# BlueFly-Shield_v10.net
KiCad netlist of a schematic drawn in EAGLE
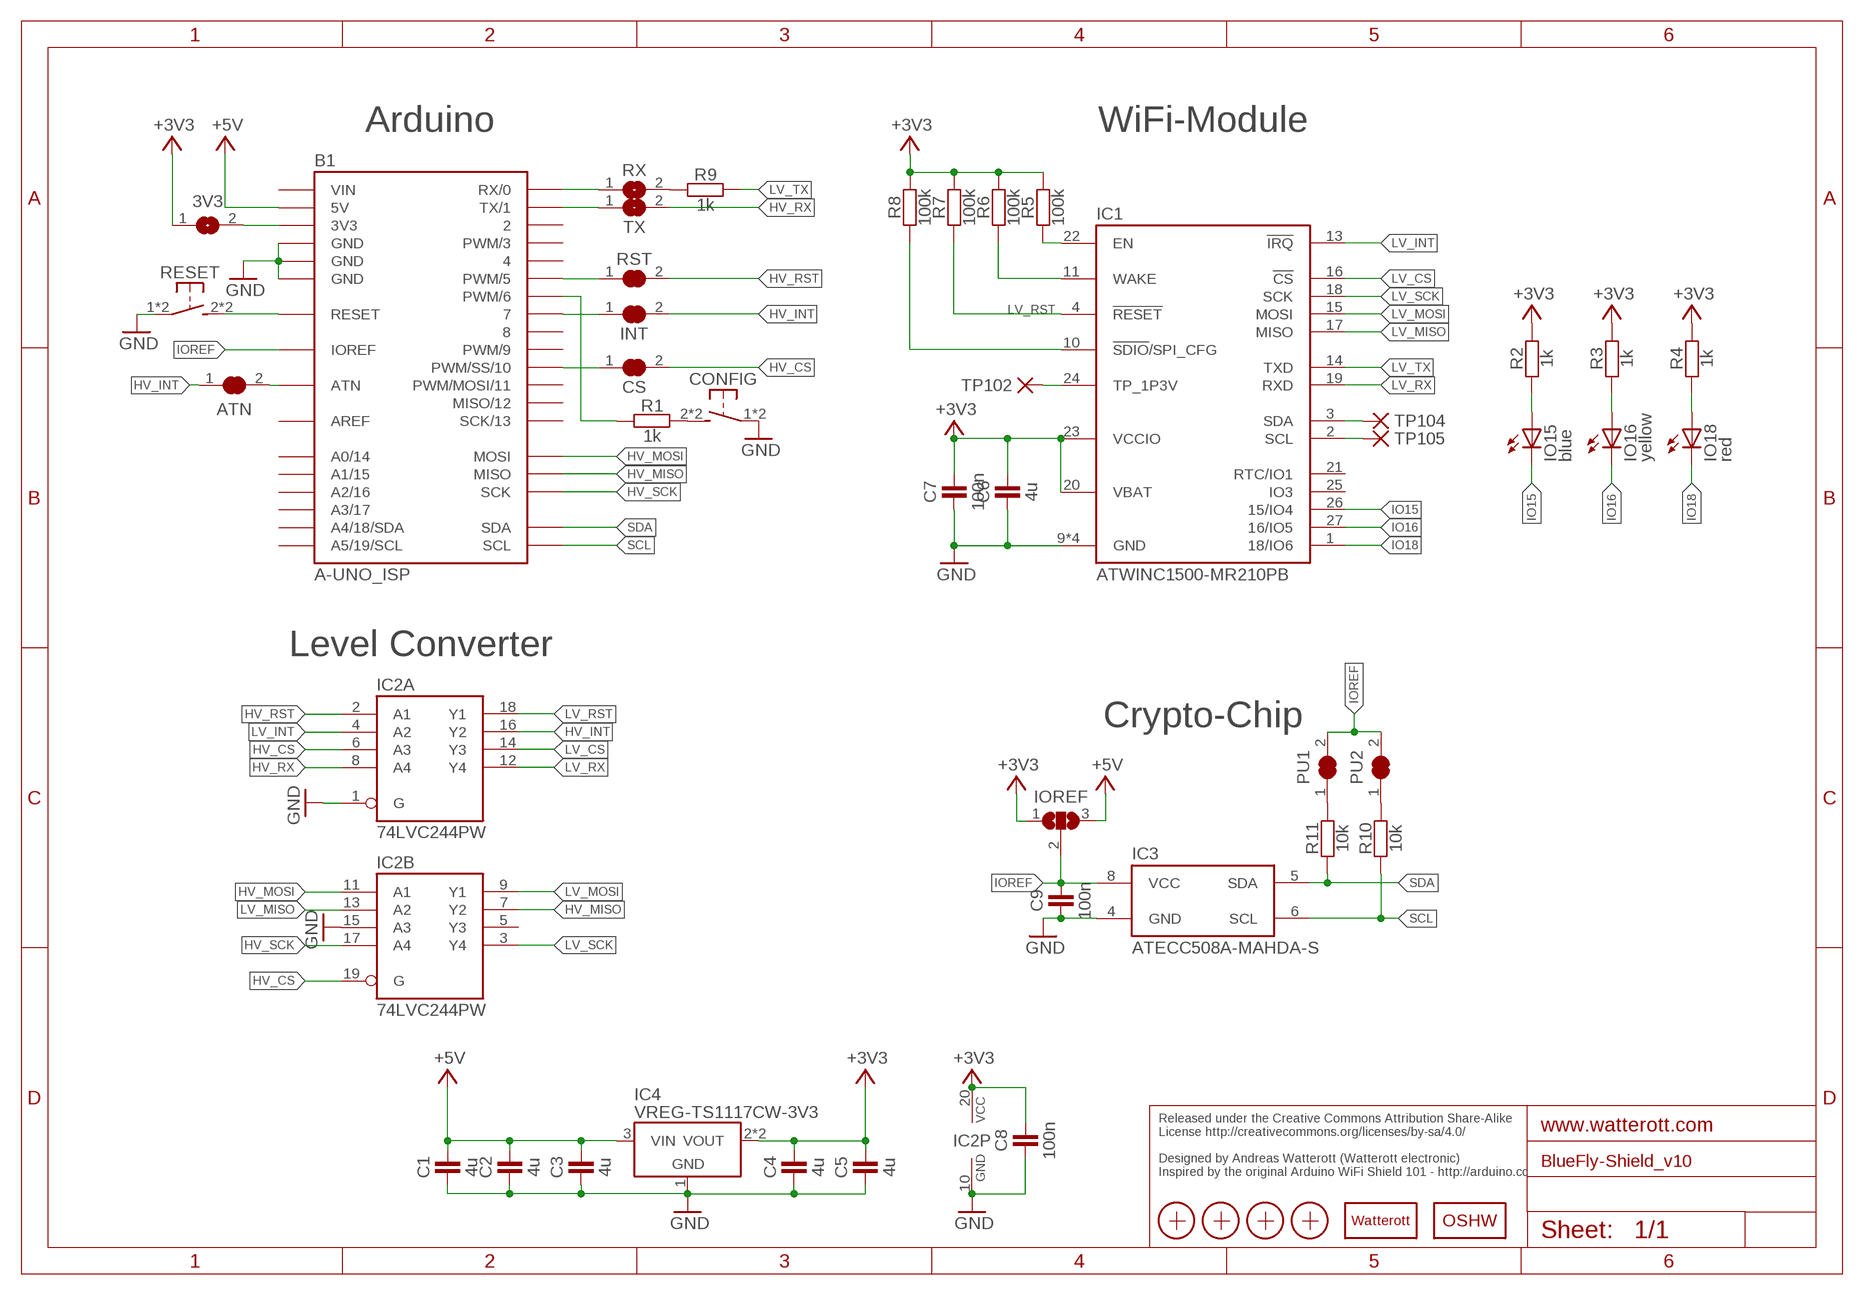
[diagram p0: schematic, sheet 1]

(export (version "E")
  (design (tool "Eeschema 10.0.6"))
  (components
    (comp (ref "3V3")
      (value "JUMPER2-0603-NC")
      (footprint "eagle-import:JUMPER2-0603_NC")
      (libsource (lib "eagle-import") (part "JUMPER2-0603-NC"))
    )
    (comp (ref "ATN")
      (value "JUMPER2-0603-NC")
      (footprint "eagle-import:JUMPER2-0603_NC")
      (libsource (lib "eagle-import") (part "JUMPER2-0603-NC"))
    )
    (comp (ref "B1")
      (value "A-UNO_ISP")
      (footprint "eagle-import:A-UNO-ISP")
      (libsource (lib "eagle-import") (part "A-UNO_ISP"))
    )
    (comp (ref "C1")
      (value "4u")
      (footprint "eagle-import:C0603")
      (libsource (lib "eagle-import") (part "CAPACITOR-0603"))
    )
    (comp (ref "C2")
      (value "4u")
      (footprint "eagle-import:C0603")
      (libsource (lib "eagle-import") (part "CAPACITOR-0603"))
    )
    (comp (ref "C3")
      (value "4u")
      (footprint "eagle-import:C0603")
      (libsource (lib "eagle-import") (part "CAPACITOR-0603"))
    )
    (comp (ref "C4")
      (value "4u")
      (footprint "eagle-import:C0603")
      (libsource (lib "eagle-import") (part "CAPACITOR-0603"))
    )
    (comp (ref "C5")
      (value "4u")
      (footprint "eagle-import:C0603")
      (libsource (lib "eagle-import") (part "CAPACITOR-0603"))
    )
    (comp (ref "C6")
      (value "4u")
      (footprint "eagle-import:C0603")
      (libsource (lib "eagle-import") (part "CAPACITOR-0603"))
    )
    (comp (ref "C7")
      (value "100n")
      (footprint "eagle-import:C0603")
      (libsource (lib "eagle-import") (part "CAPACITOR-0603"))
    )
    (comp (ref "C8")
      (value "100n")
      (footprint "eagle-import:C0402")
      (libsource (lib "eagle-import") (part "CAPACITOR-0402"))
    )
    (comp (ref "C9")
      (value "100n")
      (footprint "eagle-import:C0402")
      (libsource (lib "eagle-import") (part "CAPACITOR-0402"))
    )
    (comp (ref "CONFIG")
      (value "SW-TACTILE-TL3315")
      (footprint "eagle-import:TL3315N")
      (libsource (lib "eagle-import") (part "SW-TACTILE-TL3315"))
    )
    (comp (ref "CS")
      (value "JUMPER2-0603-NC")
      (footprint "eagle-import:JUMPER2-0603_NC")
      (libsource (lib "eagle-import") (part "JUMPER2-0603-NC"))
    )
    (comp (ref "IC1")
      (value "ATWINC1500-MR210PB")
      (footprint "eagle-import:ATWINC1500-MX210")
      (libsource (lib "eagle-import") (part "ATWINC1500-MR210PB"))
    )
    (comp (ref "IC2")
      (value "74LVC244PW")
      (footprint "eagle-import:TSSOP20")
      (libsource (lib "eagle-import") (part "74244PWLVC"))
    )
    (comp (ref "IC3")
      (value "ATECC508A-MAHDA-S")
      (footprint "eagle-import:UDFN8")
      (libsource (lib "eagle-import") (part "ATECC508A-MAHDA-S"))
    )
    (comp (ref "IC4")
      (value "VREG-TS1117CW-3V3")
      (footprint "eagle-import:SOT223")
      (libsource (lib "eagle-import") (part "VREG-TS1117CW-3V3"))
    )
    (comp (ref "INT")
      (value "JUMPER2-0603-NC")
      (footprint "eagle-import:JUMPER2-0603_NC")
      (libsource (lib "eagle-import") (part "JUMPER2-0603-NC"))
    )
    (comp (ref "IO15")
      (value "blue")
      (footprint "eagle-import:C0603")
      (libsource (lib "eagle-import") (part "LED-0603"))
    )
    (comp (ref "IO16")
      (value "yellow")
      (footprint "eagle-import:C0603")
      (libsource (lib "eagle-import") (part "LED-0603"))
    )
    (comp (ref "IO18")
      (value "red")
      (footprint "eagle-import:C0603")
      (libsource (lib "eagle-import") (part "LED-0603"))
    )
    (comp (ref "IOREF")
      (value "JUMPER3-0603-NC")
      (footprint "eagle-import:JUMPER3-0603_NC")
      (libsource (lib "eagle-import") (part "JUMPER3-0603-NC"))
    )
    (comp (ref "LOGO1")
      (value "LOGO-S_PLACE_M")
      (footprint "eagle-import:SPARK_TPLACE_M")
      (libsource (lib "eagle-import") (part "LOGO-S_PLACE_M"))
    )
    (comp (ref "LOGO2")
      (value "OSHW_LOGOX0100")
      (footprint "eagle-import:OSHW_6X100")
      (libsource (lib "eagle-import") (part "OSHW_LOGOX0100"))
    )
    (comp (ref "PU1")
      (value "JUMPER2-0603-NC")
      (footprint "eagle-import:JUMPER2-0603_NC")
      (libsource (lib "eagle-import") (part "JUMPER2-0603-NC"))
    )
    (comp (ref "PU2")
      (value "JUMPER2-0603-NC")
      (footprint "eagle-import:JUMPER2-0603_NC")
      (libsource (lib "eagle-import") (part "JUMPER2-0603-NC"))
    )
    (comp (ref "R1")
      (value "1k")
      (footprint "eagle-import:C0402")
      (libsource (lib "eagle-import") (part "RESISTOR-0402"))
    )
    (comp (ref "R2")
      (value "1k")
      (footprint "eagle-import:C0402")
      (libsource (lib "eagle-import") (part "RESISTOR-0402"))
    )
    (comp (ref "R3")
      (value "1k")
      (footprint "eagle-import:C0402")
      (libsource (lib "eagle-import") (part "RESISTOR-0402"))
    )
    (comp (ref "R4")
      (value "1k")
      (footprint "eagle-import:C0402")
      (libsource (lib "eagle-import") (part "RESISTOR-0402"))
    )
    (comp (ref "R5")
      (value "100k")
      (footprint "eagle-import:C0402")
      (libsource (lib "eagle-import") (part "RESISTOR-0402"))
    )
    (comp (ref "R6")
      (value "100k")
      (footprint "eagle-import:C0402")
      (libsource (lib "eagle-import") (part "RESISTOR-0402"))
    )
    (comp (ref "R7")
      (value "100k")
      (footprint "eagle-import:C0402")
      (libsource (lib "eagle-import") (part "RESISTOR-0402"))
    )
    (comp (ref "R8")
      (value "100k")
      (footprint "eagle-import:C0402")
      (libsource (lib "eagle-import") (part "RESISTOR-0402"))
    )
    (comp (ref "R9")
      (value "1k")
      (footprint "eagle-import:C0402")
      (libsource (lib "eagle-import") (part "RESISTOR-0402"))
    )
    (comp (ref "R10")
      (value "10k")
      (footprint "eagle-import:C0402")
      (libsource (lib "eagle-import") (part "RESISTOR-0402"))
    )
    (comp (ref "R11")
      (value "10k")
      (footprint "eagle-import:C0402")
      (libsource (lib "eagle-import") (part "RESISTOR-0402"))
    )
    (comp (ref "RESET")
      (value "SW-TACTILE-TL3315")
      (footprint "eagle-import:TL3315N")
      (libsource (lib "eagle-import") (part "SW-TACTILE-TL3315"))
    )
    (comp (ref "RST")
      (value "JUMPER2-0603-NC")
      (footprint "eagle-import:JUMPER2-0603_NC")
      (libsource (lib "eagle-import") (part "JUMPER2-0603-NC"))
    )
    (comp (ref "RX")
      (value "JUMPER2-0603-NC")
      (footprint "eagle-import:JUMPER2-0603_NC")
      (libsource (lib "eagle-import") (part "JUMPER2-0603-NC"))
    )
    (comp (ref "TP102")
      (value "PAD-1.27X1.27_NC")
      (footprint "eagle-import:PAD-1.27X1.27_NC")
      (libsource (lib "eagle-import") (part "PAD-1.27X1.27_NC"))
    )
    (comp (ref "TP104")
      (value "PAD-1.27X1.27_NC")
      (footprint "eagle-import:PAD-1.27X1.27_NC")
      (libsource (lib "eagle-import") (part "PAD-1.27X1.27_NC"))
    )
    (comp (ref "TP105")
      (value "PAD-1.27X1.27_NC")
      (footprint "eagle-import:PAD-1.27X1.27_NC")
      (libsource (lib "eagle-import") (part "PAD-1.27X1.27_NC"))
    )
    (comp (ref "TX")
      (value "JUMPER2-0603-NC")
      (footprint "eagle-import:JUMPER2-0603_NC")
      (libsource (lib "eagle-import") (part "JUMPER2-0603-NC"))
    )
    (comp (ref "X1")
      (value "PASSER-07")
      (footprint "eagle-import:PASSER_07MM")
      (libsource (lib "eagle-import") (part "PASSER-07"))
    )
    (comp (ref "X2")
      (value "PASSER-07")
      (footprint "eagle-import:PASSER_07MM")
      (libsource (lib "eagle-import") (part "PASSER-07"))
    )
    (comp (ref "X3")
      (value "PASSER-07")
      (footprint "eagle-import:PASSER_07MM")
      (libsource (lib "eagle-import") (part "PASSER-07"))
    )
    (comp (ref "X4")
      (value "PASSER-07")
      (footprint "eagle-import:PASSER_07MM")
      (libsource (lib "eagle-import") (part "PASSER-07"))
    )
  )
  (nets
    (net (code "1") (name "+3V3") (class "Default")
      (node (ref "3V3") (pin "1") (pinfunction "1_1") (pintype "passive"))
      (node (ref "C4") (pin "2") (pinfunction "2_2") (pintype "passive"))
      (node (ref "C5") (pin "2") (pinfunction "2_2") (pintype "passive"))
      (node (ref "C6") (pin "2") (pinfunction "2_2") (pintype "passive"))
      (node (ref "C7") (pin "2") (pinfunction "2_2") (pintype "passive"))
      (node (ref "C8") (pin "2") (pinfunction "2_2") (pintype "passive"))
      (node (ref "IC1") (pin "20") (pinfunction "VBAT_20") (pintype "power_in"))
      (node (ref "IC1") (pin "23") (pinfunction "VCCIO_23") (pintype "power_in"))
      (node (ref "IC2") (pin "20") (pinfunction "VCC_20") (pintype "power_in"))
      (node (ref "IC4") (pin "2") (pinfunction "VOUT_2") (pintype "power_in"))
      (node (ref "IC4") (pin "4") (pinfunction "VOUT_4") (pintype "power_in"))
      (node (ref "IOREF") (pin "1") (pinfunction "1_1") (pintype "passive"))
      (node (ref "R2") (pin "2") (pinfunction "2_2") (pintype "passive"))
      (node (ref "R3") (pin "2") (pinfunction "2_2") (pintype "passive"))
      (node (ref "R4") (pin "2") (pinfunction "2_2") (pintype "passive"))
      (node (ref "R5") (pin "2") (pinfunction "2_2") (pintype "passive"))
      (node (ref "R6") (pin "2") (pinfunction "2_2") (pintype "passive"))
      (node (ref "R7") (pin "2") (pinfunction "2_2") (pintype "passive"))
      (node (ref "R8") (pin "2") (pinfunction "2_2") (pintype "passive"))
    )
    (net (code "2") (name "+5V") (class "Default")
      (node (ref "B1") (pin "5V") (pinfunction "5V_5V") (pintype "power_in"))
      (node (ref "C1") (pin "2") (pinfunction "2_2") (pintype "passive"))
      (node (ref "C2") (pin "2") (pinfunction "2_2") (pintype "passive"))
      (node (ref "C3") (pin "2") (pinfunction "2_2") (pintype "passive"))
      (node (ref "IC4") (pin "3") (pinfunction "VIN_3") (pintype "power_in"))
      (node (ref "IOREF") (pin "3") (pinfunction "3_3") (pintype "passive"))
    )
    (net (code "3") (name "/AREF") (class "Default")
      (node (ref "B1") (pin "AREF") (pinfunction "AREF_AREF") (pintype "power_in"))
    )
    (net (code "4") (name "/VIN") (class "Default")
      (node (ref "B1") (pin "VIN") (pinfunction "VIN_VIN") (pintype "power_in"))
    )
    (net (code "5") (name "GND") (class "Default")
      (node (ref "B1") (pin "GND@1") (pinfunction "GND_GND@1") (pintype "power_in"))
      (node (ref "B1") (pin "GND@2") (pinfunction "GND_GND@2") (pintype "power_in"))
      (node (ref "B1") (pin "GND@3") (pinfunction "GND_GND@3") (pintype "power_in"))
      (node (ref "C1") (pin "1") (pinfunction "1_1") (pintype "passive"))
      (node (ref "C2") (pin "1") (pinfunction "1_1") (pintype "passive"))
      (node (ref "C3") (pin "1") (pinfunction "1_1") (pintype "passive"))
      (node (ref "C4") (pin "1") (pinfunction "1_1") (pintype "passive"))
      (node (ref "C5") (pin "1") (pinfunction "1_1") (pintype "passive"))
      (node (ref "C6") (pin "1") (pinfunction "1_1") (pintype "passive"))
      (node (ref "C7") (pin "1") (pinfunction "1_1") (pintype "passive"))
      (node (ref "C8") (pin "1") (pinfunction "1_1") (pintype "passive"))
      (node (ref "C9") (pin "1") (pinfunction "1_1") (pintype "passive"))
      (node (ref "CONFIG") (pin "1") (pinfunction "P1_1") (pintype "passive"))
      (node (ref "CONFIG") (pin "4") (pinfunction "P1_4") (pintype "passive"))
      (node (ref "IC1") (pin "12") (pinfunction "GND_12") (pintype "power_in"))
      (node (ref "IC1") (pin "28") (pinfunction "GND_28") (pintype "power_in"))
      (node (ref "IC1") (pin "9") (pinfunction "GND_9") (pintype "power_in"))
      (node (ref "IC1") (pin "GND") (pinfunction "GND_GND") (pintype "power_in"))
      (node (ref "IC2") (pin "1") (pinfunction "G_1") (pintype "input"))
      (node (ref "IC2") (pin "10") (pinfunction "GND_10") (pintype "power_in"))
      (node (ref "IC2") (pin "15") (pinfunction "A3_15") (pintype "input"))
      (node (ref "IC3") (pin "4") (pinfunction "GND_4") (pintype "power_in"))
      (node (ref "IC4") (pin "1") (pinfunction "GND_1") (pintype "power_in"))
      (node (ref "RESET") (pin "1") (pinfunction "P1_1") (pintype "passive"))
      (node (ref "RESET") (pin "4") (pinfunction "P1_4") (pintype "passive"))
    )
    (net (code "6") (name "HV_CS") (class "Default")
      (node (ref "CS") (pin "2") (pinfunction "2_2") (pintype "passive"))
      (node (ref "IC2") (pin "19") (pinfunction "G_19") (pintype "input"))
      (node (ref "IC2") (pin "6") (pinfunction "A3_6") (pintype "input"))
    )
    (net (code "7") (name "HV_INT") (class "Default")
      (node (ref "ATN") (pin "1") (pinfunction "1_1") (pintype "passive"))
      (node (ref "IC2") (pin "16") (pinfunction "Y2_16") (pintype "tri_state"))
      (node (ref "INT") (pin "2") (pinfunction "2_2") (pintype "passive"))
    )
    (net (code "8") (name "HV_MISO") (class "Default")
      (node (ref "B1") (pin "MISO") (pinfunction "MISO_MISO") (pintype "bidirectional"))
      (node (ref "IC2") (pin "7") (pinfunction "Y2_7") (pintype "tri_state"))
    )
    (net (code "9") (name "HV_MOSI") (class "Default")
      (node (ref "B1") (pin "MOSI") (pinfunction "MOSI_MOSI") (pintype "bidirectional"))
      (node (ref "IC2") (pin "11") (pinfunction "A1_11") (pintype "input"))
    )
    (net (code "10") (name "HV_RST") (class "Default")
      (node (ref "IC2") (pin "2") (pinfunction "A1_2") (pintype "input"))
      (node (ref "RST") (pin "2") (pinfunction "2_2") (pintype "passive"))
    )
    (net (code "11") (name "HV_RX") (class "Default")
      (node (ref "IC2") (pin "8") (pinfunction "A4_8") (pintype "input"))
      (node (ref "TX") (pin "2") (pinfunction "2_2") (pintype "passive"))
    )
    (net (code "12") (name "HV_SCK") (class "Default")
      (node (ref "B1") (pin "SCK") (pinfunction "SCK_SCK") (pintype "bidirectional"))
      (node (ref "IC2") (pin "17") (pinfunction "A4_17") (pintype "input"))
    )
    (net (code "13") (name "IO15") (class "Default")
      (node (ref "IC1") (pin "26") (pinfunction "15/IO4_26") (pintype "bidirectional"))
      (node (ref "IO15") (pin "C") (pinfunction "C_C") (pintype "passive"))
    )
    (net (code "14") (name "IO16") (class "Default")
      (node (ref "IC1") (pin "27") (pinfunction "16/IO5_27") (pintype "bidirectional"))
      (node (ref "IO16") (pin "C") (pinfunction "C_C") (pintype "passive"))
    )
    (net (code "15") (name "IO18") (class "Default")
      (node (ref "IC1") (pin "1") (pinfunction "18/IO6_1") (pintype "bidirectional"))
      (node (ref "IO18") (pin "C") (pinfunction "C_C") (pintype "passive"))
    )
    (net (code "16") (name "IOREF") (class "Default")
      (node (ref "B1") (pin "IOREF") (pinfunction "IOREF_IOREF") (pintype "power_in"))
      (node (ref "C9") (pin "2") (pinfunction "2_2") (pintype "passive"))
      (node (ref "IC3") (pin "8") (pinfunction "VCC_8") (pintype "power_in"))
      (node (ref "IOREF") (pin "2") (pinfunction "2_2") (pintype "passive"))
      (node (ref "PU1") (pin "2") (pinfunction "2_2") (pintype "passive"))
      (node (ref "PU2") (pin "2") (pinfunction "2_2") (pintype "passive"))
    )
    (net (code "17") (name "LV_CS") (class "Default")
      (node (ref "IC1") (pin "16") (pinfunction "~{CS}_16") (pintype "input"))
      (node (ref "IC2") (pin "14") (pinfunction "Y3_14") (pintype "tri_state"))
    )
    (net (code "18") (name "LV_INT") (class "Default")
      (node (ref "IC1") (pin "13") (pinfunction "~{IRQ}_13") (pintype "output"))
      (node (ref "IC2") (pin "4") (pinfunction "A2_4") (pintype "input"))
    )
    (net (code "19") (name "LV_MISO") (class "Default")
      (node (ref "IC1") (pin "17") (pinfunction "MISO_17") (pintype "output"))
      (node (ref "IC2") (pin "13") (pinfunction "A2_13") (pintype "input"))
    )
    (net (code "20") (name "LV_MOSI") (class "Default")
      (node (ref "IC1") (pin "15") (pinfunction "MOSI_15") (pintype "input"))
      (node (ref "IC2") (pin "9") (pinfunction "Y1_9") (pintype "tri_state"))
    )
    (net (code "21") (name "LV_RST") (class "Default")
      (node (ref "IC1") (pin "4") (pinfunction "~{RESET}_4") (pintype "input"))
      (node (ref "IC2") (pin "18") (pinfunction "Y1_18") (pintype "tri_state"))
      (node (ref "R7") (pin "1") (pinfunction "1_1") (pintype "passive"))
    )
    (net (code "22") (name "LV_RX") (class "Default")
      (node (ref "IC1") (pin "19") (pinfunction "RXD_19") (pintype "input"))
      (node (ref "IC2") (pin "12") (pinfunction "Y4_12") (pintype "tri_state"))
    )
    (net (code "23") (name "LV_SCK") (class "Default")
      (node (ref "IC1") (pin "18") (pinfunction "SCK_18") (pintype "input"))
      (node (ref "IC2") (pin "3") (pinfunction "Y4_3") (pintype "tri_state"))
    )
    (net (code "24") (name "LV_TX") (class "Default")
      (node (ref "IC1") (pin "14") (pinfunction "TXD_14") (pintype "output"))
      (node (ref "R9") (pin "2") (pinfunction "2_2") (pintype "passive"))
    )
    (net (code "25") (name "Net-(3V3-Pad2)") (class "Default")
      (node (ref "3V3") (pin "2") (pinfunction "2_2") (pintype "passive"))
      (node (ref "B1") (pin "3V3") (pinfunction "3V3_3V3") (pintype "power_in"))
    )
    (net (code "26") (name "Net-(ATN-Pad2)") (class "Default")
      (node (ref "ATN") (pin "2") (pinfunction "2_2") (pintype "passive"))
      (node (ref "B1") (pin "ATN") (pinfunction "ATN_ATN") (pintype "bidirectional"))
    )
    (net (code "27") (name "Net-(B1-PWM{slash}5)") (class "Default")
      (node (ref "B1") (pin "5") (pinfunction "PWM/5_5") (pintype "bidirectional"))
      (node (ref "RST") (pin "1") (pinfunction "1_1") (pintype "passive"))
    )
    (net (code "28") (name "Net-(B1-PWM{slash}6)") (class "Default")
      (node (ref "B1") (pin "6") (pinfunction "PWM/6_6") (pintype "bidirectional"))
      (node (ref "R1") (pin "1") (pinfunction "1_1") (pintype "passive"))
    )
    (net (code "29") (name "Net-(B1-PWM{slash}SS{slash}10)") (class "Default")
      (node (ref "B1") (pin "10") (pinfunction "PWM/SS/10_10") (pintype "bidirectional"))
      (node (ref "CS") (pin "1") (pinfunction "1_1") (pintype "passive"))
    )
    (net (code "30") (name "Net-(B1-Pad7)") (class "Default")
      (node (ref "B1") (pin "7") (pinfunction "7_7") (pintype "bidirectional"))
      (node (ref "INT") (pin "1") (pinfunction "1_1") (pintype "passive"))
    )
    (net (code "31") (name "Net-(B1-RESET)") (class "Default")
      (node (ref "B1") (pin "RST@1") (pinfunction "RESET_RST@1") (pintype "bidirectional"))
      (node (ref "RESET") (pin "2") (pinfunction "S1_2") (pintype "passive"))
      (node (ref "RESET") (pin "3") (pinfunction "S1_3") (pintype "passive"))
    )
    (net (code "32") (name "Net-(B1-RX{slash}0)") (class "Default")
      (node (ref "B1") (pin "0") (pinfunction "RX/0_0") (pintype "bidirectional"))
      (node (ref "RX") (pin "1") (pinfunction "1_1") (pintype "passive"))
    )
    (net (code "33") (name "Net-(B1-TX{slash}1)") (class "Default")
      (node (ref "B1") (pin "1") (pinfunction "TX/1_1") (pintype "bidirectional"))
      (node (ref "TX") (pin "1") (pinfunction "1_1") (pintype "passive"))
    )
    (net (code "34") (name "Net-(CONFIG-S1-Pad2)") (class "Default")
      (node (ref "CONFIG") (pin "2") (pinfunction "S1_2") (pintype "passive"))
      (node (ref "CONFIG") (pin "3") (pinfunction "S1_3") (pintype "passive"))
      (node (ref "R1") (pin "2") (pinfunction "2_2") (pintype "passive"))
    )
    (net (code "35") (name "Net-(IC1-EN)") (class "Default")
      (node (ref "IC1") (pin "22") (pinfunction "EN_22") (pintype "input"))
      (node (ref "R5") (pin "1") (pinfunction "1_1") (pintype "passive"))
    )
    (net (code "36") (name "Net-(IC1-SCL)") (class "Default")
      (node (ref "IC1") (pin "2") (pinfunction "SCL_2") (pintype "bidirectional"))
      (node (ref "TP105") (pin "1") (pinfunction "P_1") (pintype "passive"))
    )
    (net (code "37") (name "Net-(IC1-SDA)") (class "Default")
      (node (ref "IC1") (pin "3") (pinfunction "SDA_3") (pintype "bidirectional"))
      (node (ref "TP104") (pin "1") (pinfunction "P_1") (pintype "passive"))
    )
    (net (code "38") (name "Net-(IC1-TP_1P3V)") (class "Default")
      (node (ref "IC1") (pin "24") (pinfunction "TP_1P3V_24") (pintype "bidirectional"))
      (node (ref "TP102") (pin "1") (pinfunction "P_1") (pintype "passive"))
    )
    (net (code "39") (name "Net-(IC1-WAKE)") (class "Default")
      (node (ref "IC1") (pin "11") (pinfunction "WAKE_11") (pintype "input"))
      (node (ref "R6") (pin "1") (pinfunction "1_1") (pintype "passive"))
    )
    (net (code "40") (name "Net-(IC1-~{SDIO}{slash}SPI_CFG)") (class "Default")
      (node (ref "IC1") (pin "10") (pinfunction "~{SDIO}/SPI_CFG_10") (pintype "input"))
      (node (ref "R8") (pin "1") (pinfunction "1_1") (pintype "passive"))
    )
    (net (code "41") (name "Net-(IO15-PadA)") (class "Default")
      (node (ref "IO15") (pin "A") (pinfunction "A_A") (pintype "passive"))
      (node (ref "R2") (pin "1") (pinfunction "1_1") (pintype "passive"))
    )
    (net (code "42") (name "Net-(IO16-PadA)") (class "Default")
      (node (ref "IO16") (pin "A") (pinfunction "A_A") (pintype "passive"))
      (node (ref "R3") (pin "1") (pinfunction "1_1") (pintype "passive"))
    )
    (net (code "43") (name "Net-(IO18-PadA)") (class "Default")
      (node (ref "IO18") (pin "A") (pinfunction "A_A") (pintype "passive"))
      (node (ref "R4") (pin "1") (pinfunction "1_1") (pintype "passive"))
    )
    (net (code "44") (name "Net-(PU1-Pad1)") (class "Default")
      (node (ref "PU1") (pin "1") (pinfunction "1_1") (pintype "passive"))
      (node (ref "R11") (pin "2") (pinfunction "2_2") (pintype "passive"))
    )
    (net (code "45") (name "Net-(PU2-Pad1)") (class "Default")
      (node (ref "PU2") (pin "1") (pinfunction "1_1") (pintype "passive"))
      (node (ref "R10") (pin "2") (pinfunction "2_2") (pintype "passive"))
    )
    (net (code "46") (name "Net-(R9-Pad1)") (class "Default")
      (node (ref "R9") (pin "1") (pinfunction "1_1") (pintype "passive"))
      (node (ref "RX") (pin "2") (pinfunction "2_2") (pintype "passive"))
    )
    (net (code "47") (name "SCL") (class "Default")
      (node (ref "B1") (pin "SCL") (pinfunction "SCL_SCL") (pintype "bidirectional"))
      (node (ref "IC3") (pin "6") (pinfunction "SCL_6") (pintype "bidirectional"))
      (node (ref "R10") (pin "1") (pinfunction "1_1") (pintype "passive"))
    )
    (net (code "48") (name "SDA") (class "Default")
      (node (ref "B1") (pin "SDA") (pinfunction "SDA_SDA") (pintype "bidirectional"))
      (node (ref "IC3") (pin "5") (pinfunction "SDA_5") (pintype "bidirectional"))
      (node (ref "R11") (pin "1") (pinfunction "1_1") (pintype "passive"))
    )
    (net (code "49") (name "unconnected-(B1-A0{slash}14-PadA0)") (class "Default")
      (node (ref "B1") (pin "A0") (pinfunction "A0/14_A0") (pintype "bidirectional"))
    )
    (net (code "50") (name "unconnected-(B1-A1{slash}15-PadA1)") (class "Default")
      (node (ref "B1") (pin "A1") (pinfunction "A1/15_A1") (pintype "bidirectional"))
    )
    (net (code "51") (name "unconnected-(B1-A2{slash}16-PadA2)") (class "Default")
      (node (ref "B1") (pin "A2") (pinfunction "A2/16_A2") (pintype "bidirectional"))
    )
    (net (code "52") (name "unconnected-(B1-A3{slash}17-PadA3)") (class "Default")
      (node (ref "B1") (pin "A3") (pinfunction "A3/17_A3") (pintype "bidirectional"))
    )
    (net (code "53") (name "unconnected-(B1-A4{slash}18{slash}SDA-PadA4)") (class "Default")
      (node (ref "B1") (pin "A4") (pinfunction "A4/18/SDA_A4") (pintype "bidirectional"))
    )
    (net (code "54") (name "unconnected-(B1-A5{slash}19{slash}SCL-PadA5)") (class "Default")
      (node (ref "B1") (pin "A5") (pinfunction "A5/19/SCL_A5") (pintype "bidirectional"))
    )
    (net (code "55") (name "unconnected-(B1-MISO{slash}12-Pad12)") (class "Default")
      (node (ref "B1") (pin "12") (pinfunction "MISO/12_12") (pintype "bidirectional"))
    )
    (net (code "56") (name "unconnected-(B1-PWM{slash}3-Pad3)") (class "Default")
      (node (ref "B1") (pin "3") (pinfunction "PWM/3_3") (pintype "bidirectional"))
    )
    (net (code "57") (name "unconnected-(B1-PWM{slash}9-Pad9)") (class "Default")
      (node (ref "B1") (pin "9") (pinfunction "PWM/9_9") (pintype "bidirectional"))
    )
    (net (code "58") (name "unconnected-(B1-PWM{slash}MOSI{slash}11-Pad11)") (class "Default")
      (node (ref "B1") (pin "11") (pinfunction "PWM/MOSI/11_11") (pintype "bidirectional"))
    )
    (net (code "59") (name "unconnected-(B1-Pad2)") (class "Default")
      (node (ref "B1") (pin "2") (pinfunction "2_2") (pintype "bidirectional"))
    )
    (net (code "60") (name "unconnected-(B1-Pad4)") (class "Default")
      (node (ref "B1") (pin "4") (pinfunction "4_4") (pintype "bidirectional"))
    )
    (net (code "61") (name "unconnected-(B1-Pad8)") (class "Default")
      (node (ref "B1") (pin "8") (pinfunction "8_8") (pintype "bidirectional"))
    )
    (net (code "62") (name "unconnected-(B1-SCK{slash}13-Pad13)") (class "Default")
      (node (ref "B1") (pin "13") (pinfunction "SCK/13_13") (pintype "bidirectional"))
    )
    (net (code "63") (name "unconnected-(IC1-IO3-Pad25)") (class "Default")
      (node (ref "IC1") (pin "25") (pinfunction "IO3_25") (pintype "bidirectional"))
    )
    (net (code "64") (name "unconnected-(IC1-RTC{slash}IO1-Pad21)") (class "Default")
      (node (ref "IC1") (pin "21") (pinfunction "RTC/IO1_21") (pintype "input"))
    )
    (net (code "65") (name "unconnected-(IC2B-Y3-Pad5)") (class "Default")
      (node (ref "IC2") (pin "5") (pinfunction "Y3_5") (pintype "tri_state"))
    )
  )
)
